# robot.net
KiCad netlist of a schematic drawn in EAGLE
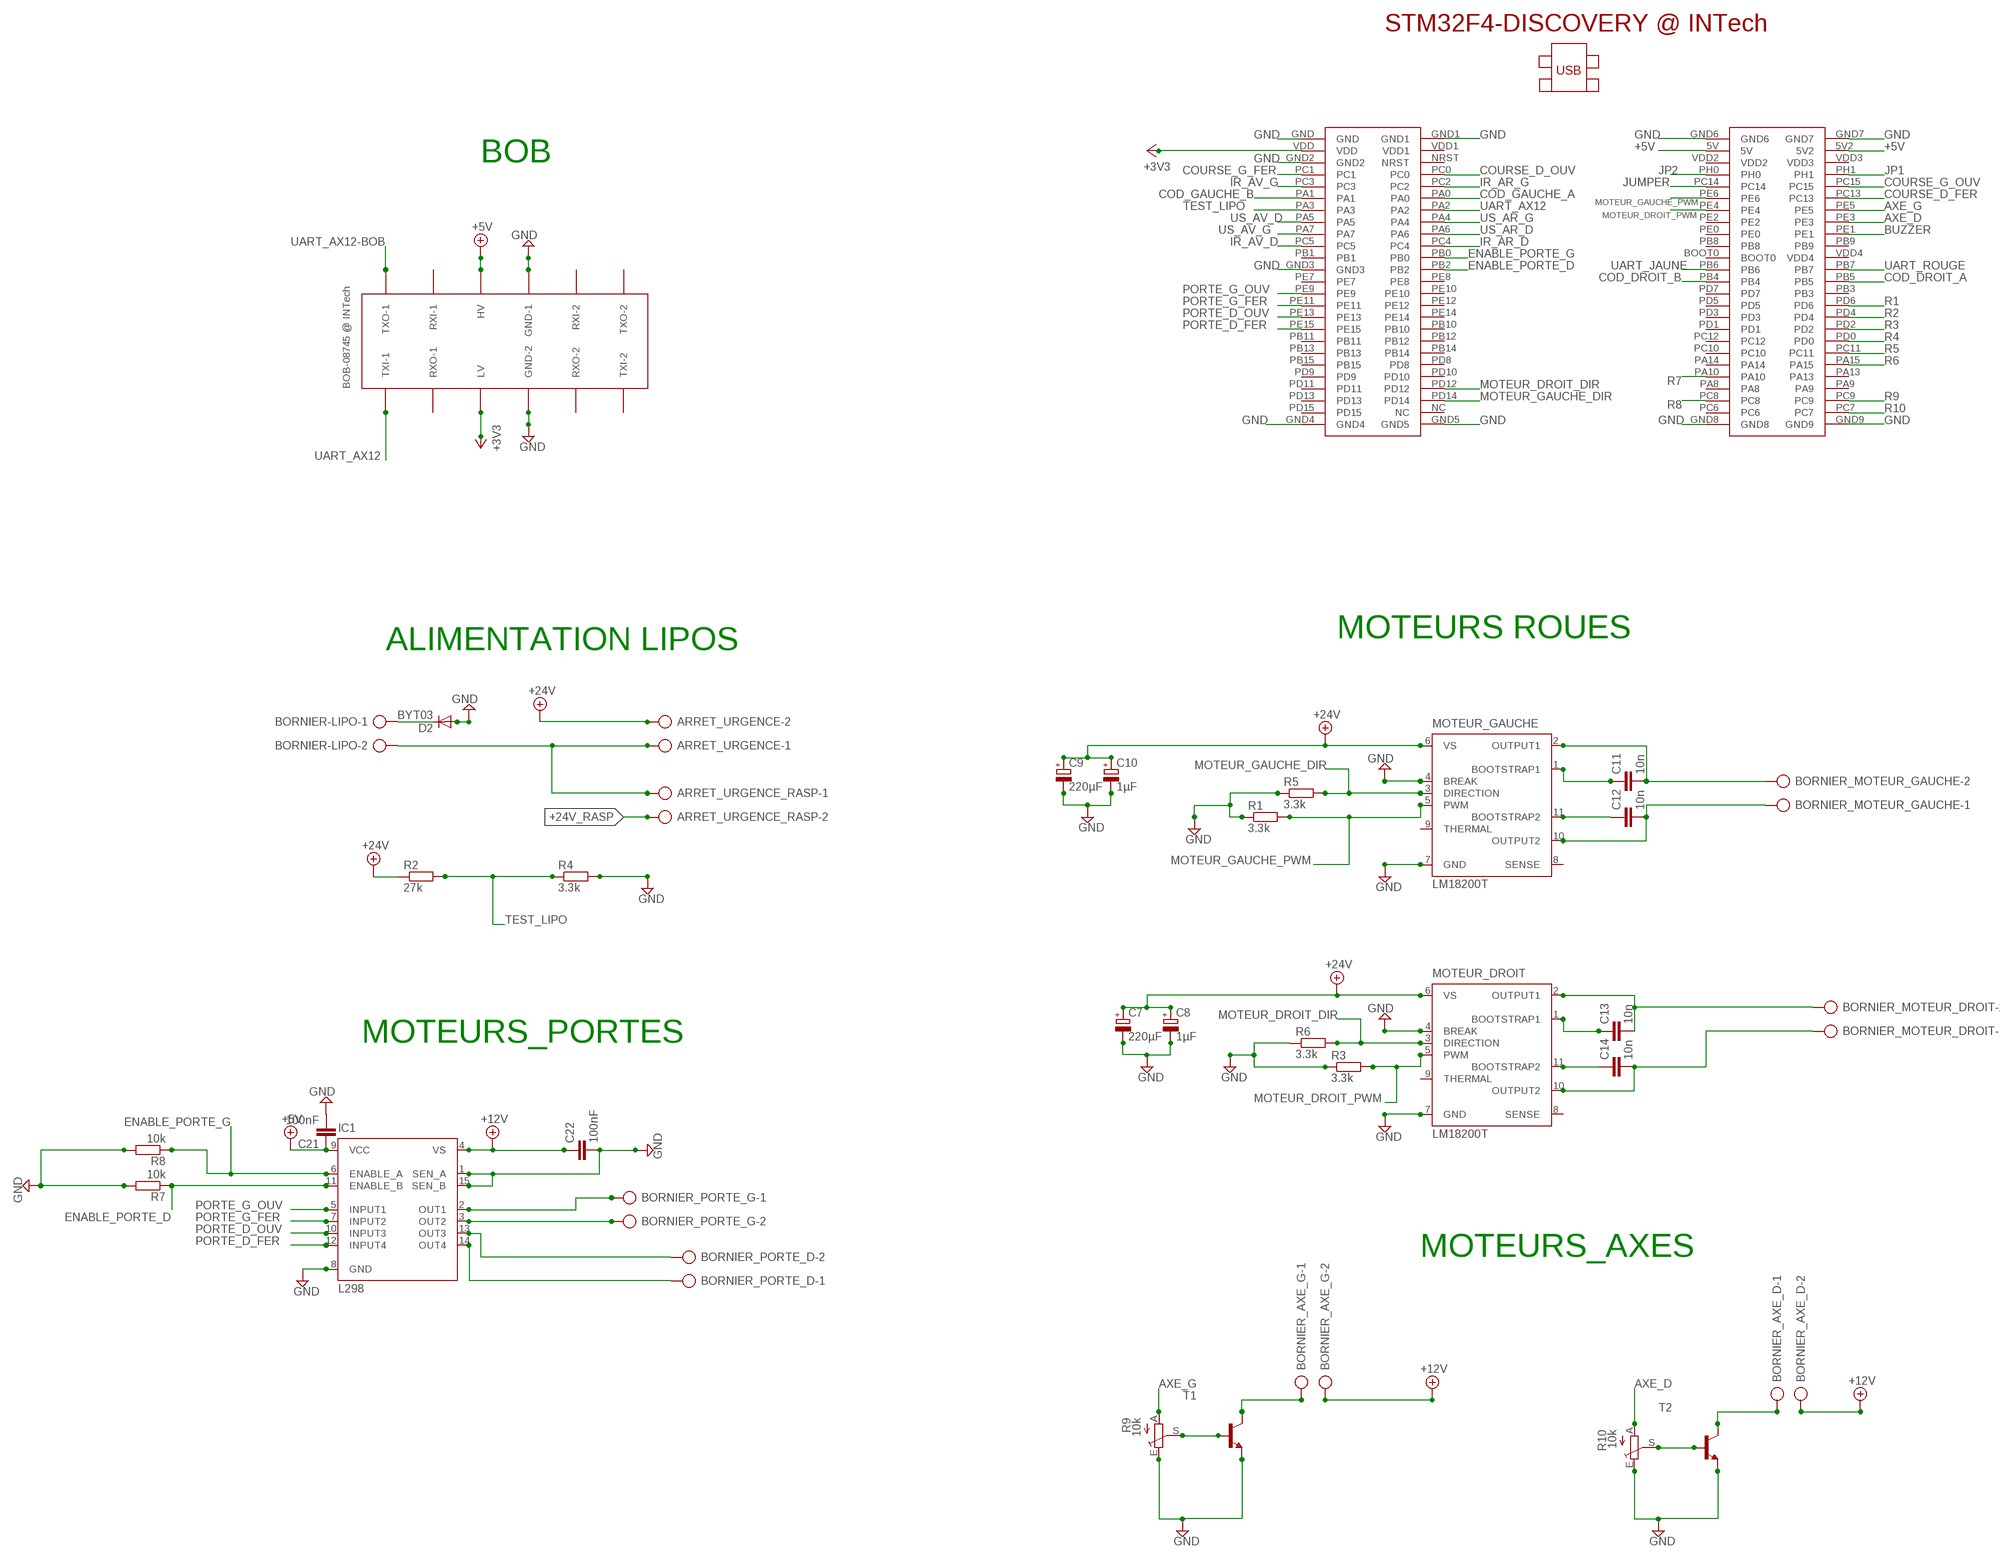
[diagram p0: schematic, sheet 1, part 1 of 2]
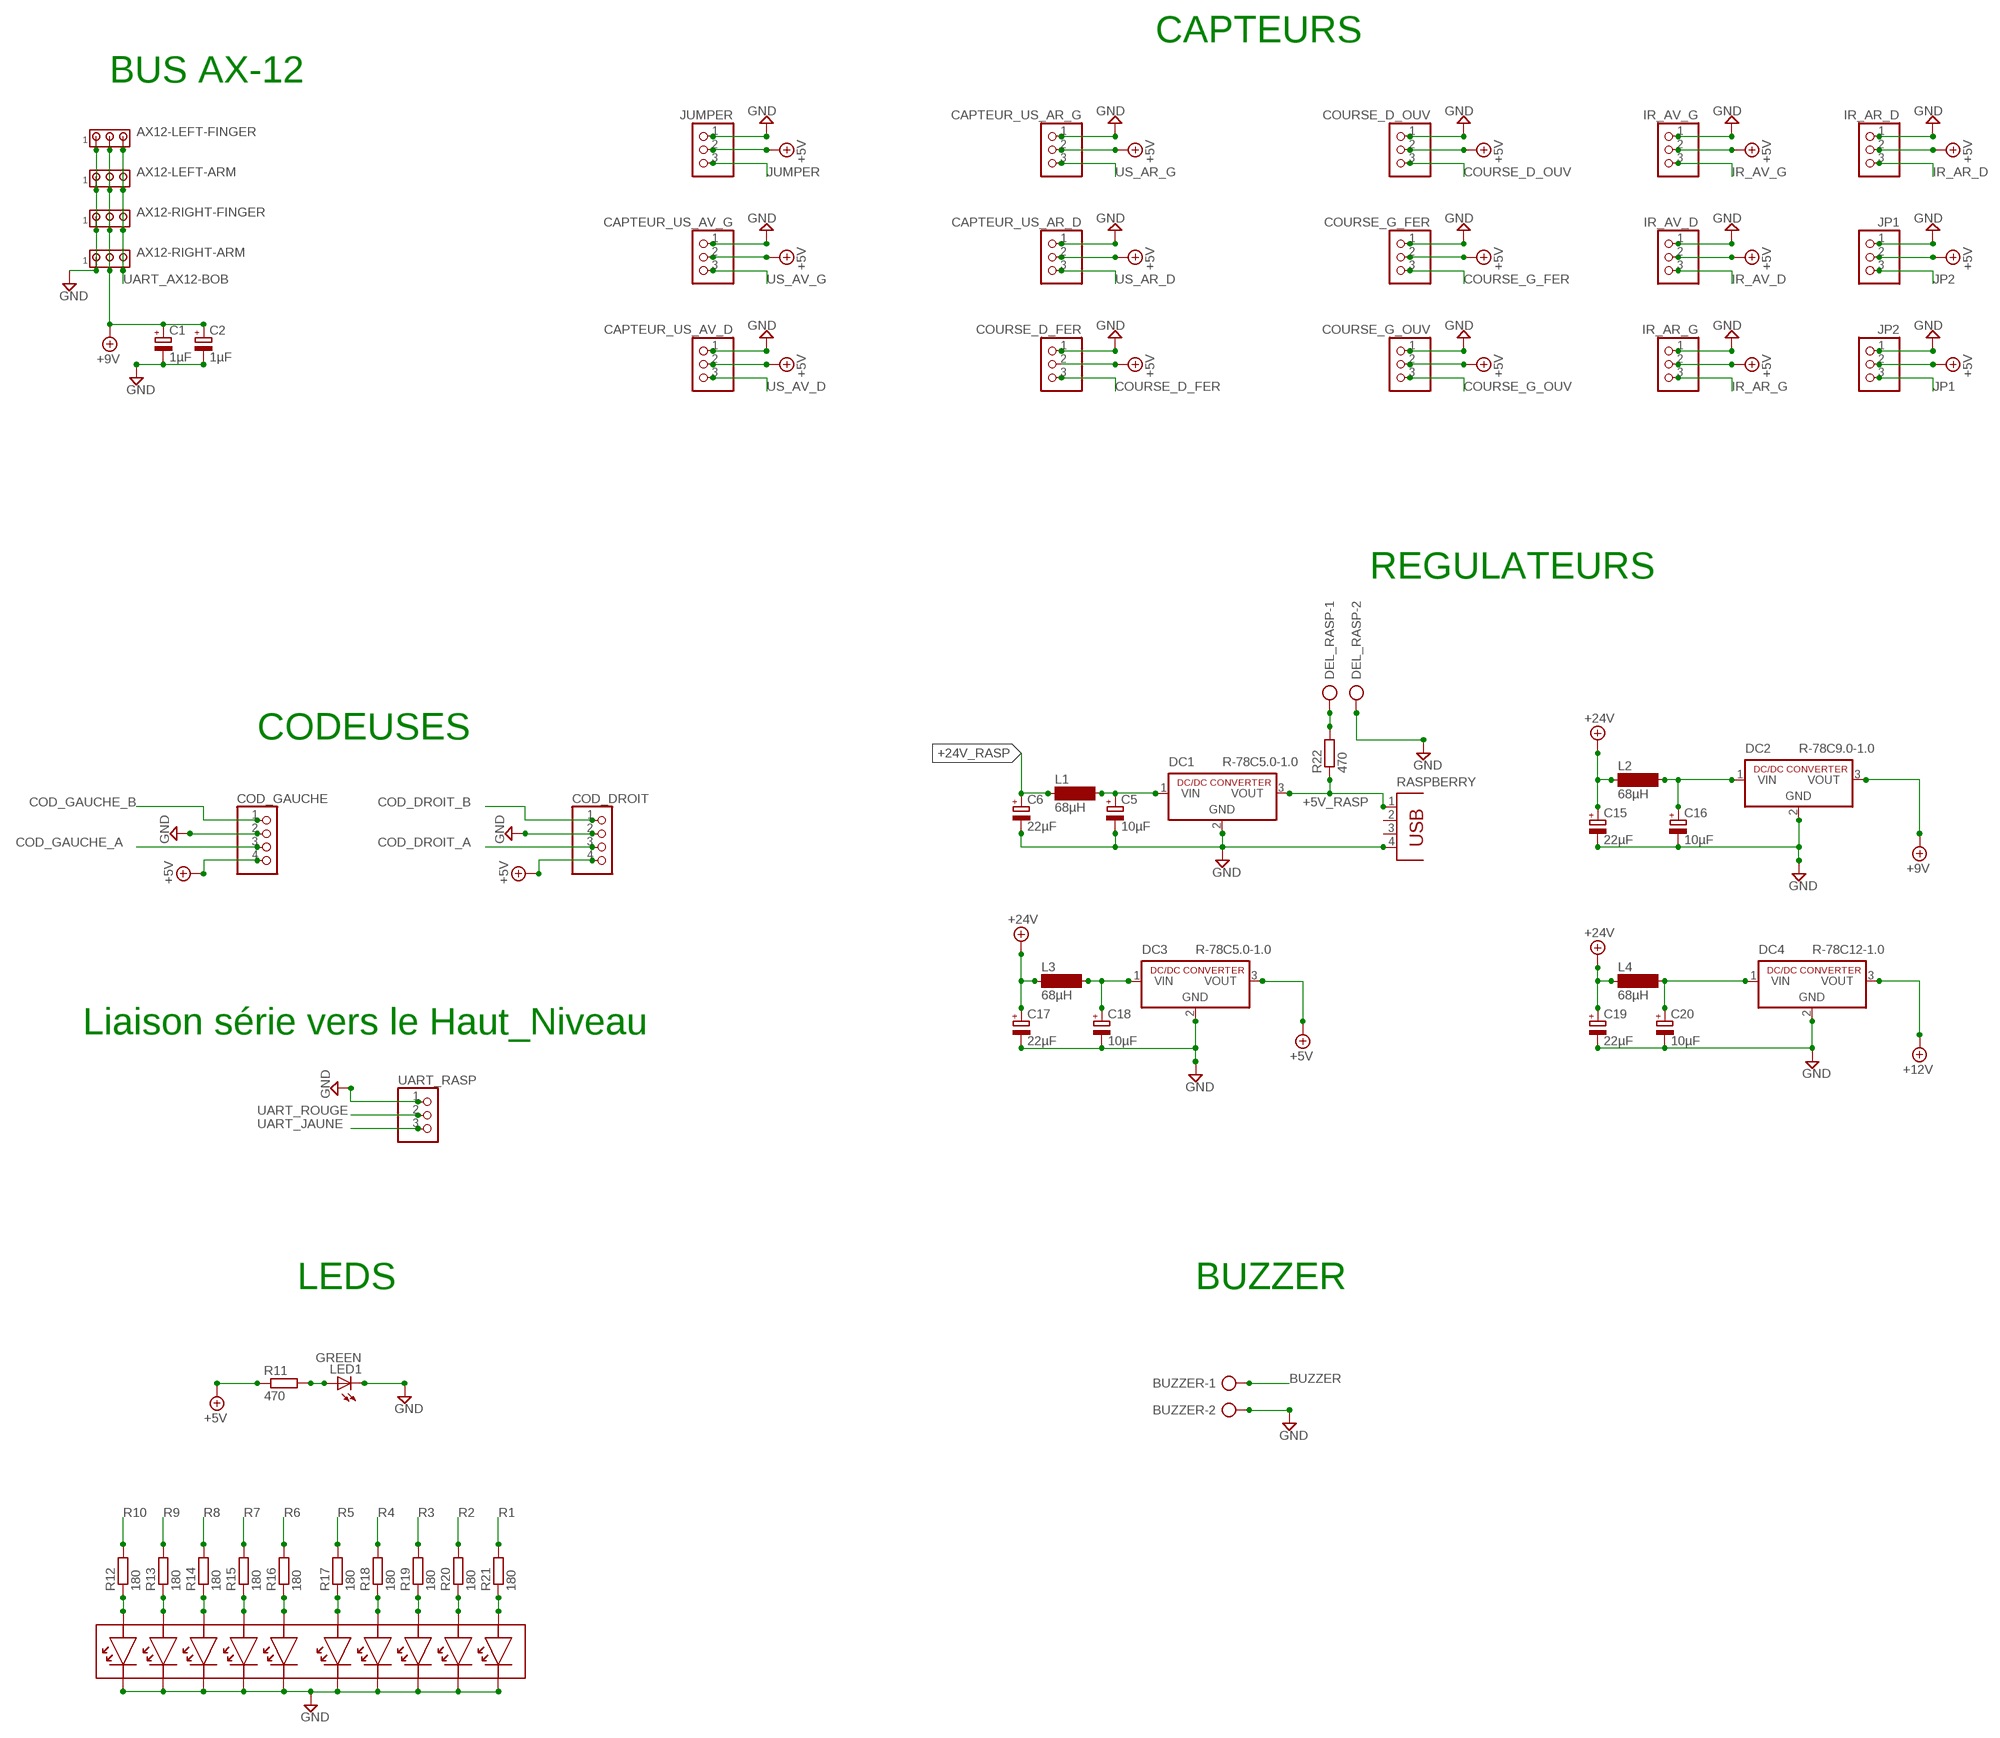
[diagram p1: schematic, sheet 1, part 2 of 2]

(export (version "E")
  (design (tool "Eeschema 10.0.6"))
  (components
    (comp (ref "ARRET_URGENCE")
      (value "AK300/2")
      (footprint "eagle-import:AK300_2")
      (libsource (lib "eagle-import") (part "AK300/2"))
    )
    (comp (ref "ARRET_URGENCE_RASP")
      (value "AK300/2")
      (footprint "eagle-import:AK300_2")
      (fields (field (name "OC_FARNELL") "unknown") (field (name "OC_NEWARK") "unknown"))
      (libsource (lib "eagle-import") (part "AK300/2"))
    )
    (comp (ref "AX12-LEFT-ARM")
      (value "MTA03-100")
      (footprint "eagle-import:10X03MTA")
      (libsource (lib "eagle-import") (part "MTA03-100"))
    )
    (comp (ref "AX12-LEFT-FINGER")
      (value "MTA03-100")
      (footprint "eagle-import:10X03MTA")
      (libsource (lib "eagle-import") (part "MTA03-100"))
    )
    (comp (ref "AX12-RIGHT-ARM")
      (value "MTA03-100")
      (footprint "eagle-import:10X03MTA")
      (libsource (lib "eagle-import") (part "MTA03-100"))
    )
    (comp (ref "AX12-RIGHT-FINGER")
      (value "MTA03-100")
      (footprint "eagle-import:10X03MTA")
      (libsource (lib "eagle-import") (part "MTA03-100"))
    )
    (comp (ref "BOB-08745")
      (value "BOB-08745")
      (footprint "eagle-import:BOB-08745")
      (libsource (lib "eagle-import") (part "BOB-08745"))
    )
    (comp (ref "BORNIER-LIPO")
      (value "AK300/2")
      (footprint "eagle-import:AK300_2")
      (libsource (lib "eagle-import") (part "AK300/2"))
    )
    (comp (ref "BORNIER_AXE_D")
      (value "AK300/2")
      (footprint "eagle-import:AK300_2")
      (fields (field (name "OC_FARNELL") "unknown") (field (name "OC_NEWARK") "unknown"))
      (libsource (lib "eagle-import") (part "AK300/2"))
    )
    (comp (ref "BORNIER_AXE_G")
      (value "AK300/2")
      (footprint "eagle-import:AK300_2")
      (fields (field (name "OC_FARNELL") "unknown") (field (name "OC_NEWARK") "unknown"))
      (libsource (lib "eagle-import") (part "AK300/2"))
    )
    (comp (ref "BORNIER_MOTEUR_DROIT")
      (value "AK300/2")
      (footprint "eagle-import:AK300_2")
      (libsource (lib "eagle-import") (part "AK300/2"))
    )
    (comp (ref "BORNIER_MOTEUR_GAUCHE")
      (value "AK300/2")
      (footprint "eagle-import:AK300_2")
      (libsource (lib "eagle-import") (part "AK300/2"))
    )
    (comp (ref "BORNIER_PORTE_D")
      (value "AK300/2")
      (footprint "eagle-import:AK300_2")
      (fields (field (name "OC_FARNELL") "unknown") (field (name "OC_NEWARK") "unknown"))
      (libsource (lib "eagle-import") (part "AK300/2"))
    )
    (comp (ref "BORNIER_PORTE_G")
      (value "AK300/2")
      (footprint "eagle-import:AK300_2")
      (fields (field (name "OC_FARNELL") "unknown") (field (name "OC_NEWARK") "unknown"))
      (libsource (lib "eagle-import") (part "AK300/2"))
    )
    (comp (ref "BUZZER")
      (value "AK300/2")
      (footprint "eagle-import:AK300_2")
      (libsource (lib "eagle-import") (part "AK300/2"))
    )
    (comp (ref "C1")
      (value "1µF")
      (footprint "eagle-import:E2,5-6E")
      (libsource (lib "eagle-import") (part "resistor_CPOL-EUE2,5-6E"))
    )
    (comp (ref "C2")
      (value "1µF")
      (footprint "eagle-import:E2,5-6E")
      (libsource (lib "eagle-import") (part "resistor_CPOL-EUE2,5-6E"))
    )
    (comp (ref "C5")
      (value "10µF")
      (footprint "eagle-import:E2,5-6E")
      (libsource (lib "eagle-import") (part "resistor_CPOL-EUE2,5-6E"))
    )
    (comp (ref "C6")
      (value "22µF")
      (footprint "eagle-import:E2,5-6E")
      (libsource (lib "eagle-import") (part "resistor_CPOL-EUE2,5-6E"))
    )
    (comp (ref "C7")
      (value "220µF")
      (footprint "eagle-import:E3,5-8")
      (libsource (lib "eagle-import") (part "CPOL-EUE3.5-8"))
    )
    (comp (ref "C8")
      (value "1µF")
      (footprint "eagle-import:E3,5-8")
      (libsource (lib "eagle-import") (part "CPOL-EUE3.5-8"))
    )
    (comp (ref "C9")
      (value "220µF")
      (footprint "eagle-import:E3,5-8")
      (libsource (lib "eagle-import") (part "CPOL-EUE3.5-8"))
    )
    (comp (ref "C10")
      (value "1µF")
      (footprint "eagle-import:E3,5-8")
      (libsource (lib "eagle-import") (part "CPOL-EUE3.5-8"))
    )
    (comp (ref "C11")
      (value "10n")
      (footprint "eagle-import:C050-025X075")
      (libsource (lib "eagle-import") (part "C-EU050-025X075"))
    )
    (comp (ref "C12")
      (value "10n")
      (footprint "eagle-import:C050-025X075")
      (libsource (lib "eagle-import") (part "C-EU050-025X075"))
    )
    (comp (ref "C13")
      (value "10n")
      (footprint "eagle-import:C050-025X075")
      (libsource (lib "eagle-import") (part "C-EU050-025X075"))
    )
    (comp (ref "C14")
      (value "10n")
      (footprint "eagle-import:C050-025X075")
      (libsource (lib "eagle-import") (part "C-EU050-025X075"))
    )
    (comp (ref "C15")
      (value "22µF")
      (footprint "eagle-import:E2,5-6E")
      (libsource (lib "eagle-import") (part "resistor_CPOL-EUE2,5-6E"))
    )
    (comp (ref "C16")
      (value "10µF")
      (footprint "eagle-import:E2,5-6E")
      (libsource (lib "eagle-import") (part "resistor_CPOL-EUE2,5-6E"))
    )
    (comp (ref "C17")
      (value "22µF")
      (footprint "eagle-import:E2,5-6E")
      (libsource (lib "eagle-import") (part "resistor_CPOL-EUE2,5-6E"))
    )
    (comp (ref "C18")
      (value "10µF")
      (footprint "eagle-import:E2,5-6E")
      (libsource (lib "eagle-import") (part "resistor_CPOL-EUE2,5-6E"))
    )
    (comp (ref "C19")
      (value "22µF")
      (footprint "eagle-import:E2,5-6E")
      (libsource (lib "eagle-import") (part "resistor_CPOL-EUE2,5-6E"))
    )
    (comp (ref "C20")
      (value "10µF")
      (footprint "eagle-import:E2,5-6E")
      (libsource (lib "eagle-import") (part "resistor_CPOL-EUE2,5-6E"))
    )
    (comp (ref "C21")
      (value "100nF")
      (footprint "eagle-import:C050-024X044")
      (libsource (lib "eagle-import") (part "resistor_C-EU050-024X044"))
    )
    (comp (ref "C22")
      (value "100nF")
      (footprint "eagle-import:C050-024X044")
      (libsource (lib "eagle-import") (part "resistor_C-EU050-024X044"))
    )
    (comp (ref "CAPTEUR_US_AR_D")
      (value "PINHD-1X3")
      (footprint "eagle-import:1X03")
      (libsource (lib "eagle-import") (part "PINHD-1X3"))
    )
    (comp (ref "CAPTEUR_US_AR_G")
      (value "PINHD-1X3")
      (footprint "eagle-import:1X03")
      (libsource (lib "eagle-import") (part "PINHD-1X3"))
    )
    (comp (ref "CAPTEUR_US_AV_D")
      (value "PINHD-1X3")
      (footprint "eagle-import:1X03")
      (libsource (lib "eagle-import") (part "PINHD-1X3"))
    )
    (comp (ref "CAPTEUR_US_AV_G")
      (value "PINHD-1X3")
      (footprint "eagle-import:1X03")
      (libsource (lib "eagle-import") (part "PINHD-1X3"))
    )
    (comp (ref "COD_DROIT")
      (value "PINHD-1X4")
      (footprint "eagle-import:1X04")
      (libsource (lib "eagle-import") (part "PINHD-1X4"))
    )
    (comp (ref "COD_GAUCHE")
      (value "PINHD-1X4")
      (footprint "eagle-import:1X04")
      (libsource (lib "eagle-import") (part "PINHD-1X4"))
    )
    (comp (ref "COURSE_D_FER")
      (value "PINHD-1X3")
      (footprint "eagle-import:1X03")
      (libsource (lib "eagle-import") (part "PINHD-1X3"))
    )
    (comp (ref "COURSE_D_OUV")
      (value "PINHD-1X3")
      (footprint "eagle-import:1X03")
      (libsource (lib "eagle-import") (part "PINHD-1X3"))
    )
    (comp (ref "COURSE_G_FER")
      (value "PINHD-1X3")
      (footprint "eagle-import:1X03")
      (libsource (lib "eagle-import") (part "PINHD-1X3"))
    )
    (comp (ref "COURSE_G_OUV")
      (value "PINHD-1X3")
      (footprint "eagle-import:1X03")
      (libsource (lib "eagle-import") (part "PINHD-1X3"))
    )
    (comp (ref "D2")
      (value "BYT03")
      (footprint "eagle-import:DO27-15")
      (libsource (lib "eagle-import") (part "BYT03"))
    )
    (comp (ref "DC1")
      (value "R-78C5.0-1.0")
      (footprint "eagle-import:SIP3")
      (libsource (lib "eagle-import") (part "R-78C-1.05.0"))
    )
    (comp (ref "DC2")
      (value "R-78C9.0-1.0")
      (footprint "eagle-import:SIP3")
      (libsource (lib "eagle-import") (part "R-78C-1.09.0"))
    )
    (comp (ref "DC3")
      (value "R-78C5.0-1.0")
      (footprint "eagle-import:SIP3")
      (libsource (lib "eagle-import") (part "R-78C-1.05.0"))
    )
    (comp (ref "DC4")
      (value "R-78C12-1.0")
      (footprint "eagle-import:SIP3")
      (libsource (lib "eagle-import") (part "R-78C-1.012"))
    )
    (comp (ref "DEL_RASP")
      (value "AK300/2")
      (footprint "eagle-import:AK300_2")
      (libsource (lib "eagle-import") (part "AK300/2"))
    )
    (comp (ref "IC1")
      (value "L298")
      (footprint "eagle-import:MULTIWATT-15")
      (fields (field (name "MPN") "L298N"))
      (libsource (lib "eagle-import") (part "L298"))
    )
    (comp (ref "IR_AR_D")
      (value "PINHD-1X3")
      (footprint "eagle-import:1X03")
      (libsource (lib "eagle-import") (part "PINHD-1X3"))
    )
    (comp (ref "IR_AR_G")
      (value "PINHD-1X3")
      (footprint "eagle-import:1X03")
      (libsource (lib "eagle-import") (part "PINHD-1X3"))
    )
    (comp (ref "IR_AV_D")
      (value "PINHD-1X3")
      (footprint "eagle-import:1X03")
      (libsource (lib "eagle-import") (part "PINHD-1X3"))
    )
    (comp (ref "IR_AV_G")
      (value "PINHD-1X3")
      (footprint "eagle-import:1X03")
      (libsource (lib "eagle-import") (part "PINHD-1X3"))
    )
    (comp (ref "JP1")
      (value "PINHD-1X3")
      (footprint "eagle-import:1X03")
      (libsource (lib "eagle-import") (part "PINHD-1X3"))
    )
    (comp (ref "JP2")
      (value "PINHD-1X3")
      (footprint "eagle-import:1X03")
      (libsource (lib "eagle-import") (part "PINHD-1X3"))
    )
    (comp (ref "JUMPER")
      (value "PINHD-1X3")
      (footprint "eagle-import:1X03")
      (libsource (lib "eagle-import") (part "PINHD-1X3"))
    )
    (comp (ref "L1")
      (value "68µH")
      (footprint "eagle-import:SD12K100")
      (libsource (lib "eagle-import") (part "SD12K100"))
    )
    (comp (ref "L2")
      (value "68µH")
      (footprint "eagle-import:SD12K100")
      (fields (field (name "OC_FARNELL") "unknown") (field (name "OC_NEWARK") "unknown"))
      (libsource (lib "eagle-import") (part "SD12K100"))
    )
    (comp (ref "L3")
      (value "68µH")
      (footprint "eagle-import:SD12K100")
      (fields (field (name "OC_FARNELL") "unknown") (field (name "OC_NEWARK") "unknown"))
      (libsource (lib "eagle-import") (part "SD12K100"))
    )
    (comp (ref "L4")
      (value "68µH")
      (footprint "eagle-import:SD12K100")
      (fields (field (name "OC_FARNELL") "unknown") (field (name "OC_NEWARK") "unknown"))
      (libsource (lib "eagle-import") (part "SD12K100"))
    )
    (comp (ref "LED1")
      (value "GREEN")
      (footprint "eagle-import:LED5MM")
      (libsource (lib "eagle-import") (part "LED5MM"))
    )
    (comp (ref "MOTEUR_DROIT")
      (value "LM18200T")
      (footprint "eagle-import:TO-220-11")
      (libsource (lib "eagle-import") (part "LM18200T"))
    )
    (comp (ref "MOTEUR_GAUCHE")
      (value "LM18200T")
      (footprint "eagle-import:TO-220-11")
      (libsource (lib "eagle-import") (part "LM18200T"))
    )
    (comp (ref "R1")
      (value "3.3k")
      (footprint "eagle-import:0207_7")
      (libsource (lib "eagle-import") (part "R-EU_0207/7"))
    )
    (comp (ref "R2")
      (value "27k")
      (footprint "eagle-import:0207_10")
      (libsource (lib "eagle-import") (part "R-EU_0207/10"))
    )
    (comp (ref "R3")
      (value "3.3k")
      (footprint "eagle-import:0207_7")
      (libsource (lib "eagle-import") (part "R-EU_0207/7"))
    )
    (comp (ref "R4")
      (value "3.3k")
      (footprint "eagle-import:0207_10")
      (libsource (lib "eagle-import") (part "R-EU_0207/10"))
    )
    (comp (ref "R5")
      (value "3.3k")
      (footprint "eagle-import:0207_10")
      (libsource (lib "eagle-import") (part "R-EU_0207/10"))
    )
    (comp (ref "R6")
      (value "3.3k")
      (footprint "eagle-import:0207_10")
      (libsource (lib "eagle-import") (part "R-EU_0207/10"))
    )
    (comp (ref "R7")
      (value "10k")
      (footprint "eagle-import:0207_10")
      (libsource (lib "eagle-import") (part "R-EU_0207/10"))
    )
    (comp (ref "R8")
      (value "10k")
      (footprint "eagle-import:0207_10")
      (libsource (lib "eagle-import") (part "R-EU_0207/10"))
    )
    (comp (ref "R9")
      (value "10k")
      (footprint "eagle-import:CA9H")
      (libsource (lib "eagle-import") (part "TRIM_EU-CA9H"))
    )
    (comp (ref "R10")
      (value "10k")
      (footprint "eagle-import:CA9H")
      (libsource (lib "eagle-import") (part "TRIM_EU-CA9H"))
    )
    (comp (ref "R11")
      (value "470")
      (footprint "eagle-import:0207_2V")
      (libsource (lib "eagle-import") (part "R-EU_0207/2V"))
    )
    (comp (ref "R12")
      (value "180")
      (footprint "eagle-import:0207_2V")
      (libsource (lib "eagle-import") (part "R-EU_0207/2V"))
    )
    (comp (ref "R13")
      (value "180")
      (footprint "eagle-import:0207_2V")
      (libsource (lib "eagle-import") (part "R-EU_0207/2V"))
    )
    (comp (ref "R14")
      (value "180")
      (footprint "eagle-import:0207_2V")
      (libsource (lib "eagle-import") (part "R-EU_0207/2V"))
    )
    (comp (ref "R15")
      (value "180")
      (footprint "eagle-import:0207_2V")
      (libsource (lib "eagle-import") (part "R-EU_0207/2V"))
    )
    (comp (ref "R16")
      (value "180")
      (footprint "eagle-import:0207_2V")
      (libsource (lib "eagle-import") (part "R-EU_0207/2V"))
    )
    (comp (ref "R17")
      (value "180")
      (footprint "eagle-import:0207_2V")
      (libsource (lib "eagle-import") (part "R-EU_0207/2V"))
    )
    (comp (ref "R18")
      (value "180")
      (footprint "eagle-import:0207_2V")
      (libsource (lib "eagle-import") (part "R-EU_0207/2V"))
    )
    (comp (ref "R19")
      (value "180")
      (footprint "eagle-import:0207_2V")
      (libsource (lib "eagle-import") (part "R-EU_0207/2V"))
    )
    (comp (ref "R20")
      (value "180")
      (footprint "eagle-import:0207_2V")
      (libsource (lib "eagle-import") (part "R-EU_0207/2V"))
    )
    (comp (ref "R21")
      (value "180")
      (footprint "eagle-import:0207_2V")
      (libsource (lib "eagle-import") (part "R-EU_0207/2V"))
    )
    (comp (ref "R22")
      (value "470")
      (footprint "eagle-import:0204_7")
      (libsource (lib "eagle-import") (part "R-EU_0204/7"))
    )
    (comp (ref "RASPBERRY")
      (value "PN87520")
      (footprint "eagle-import:PN87520")
      (libsource (lib "eagle-import") (part "PN87520"))
    )
    (comp (ref "T1")
      (value "2N5400-NPN-TO92-CBE")
      (footprint "eagle-import:TO92-CBE")
      (libsource (lib "eagle-import") (part "-NPN-TO92-CBE2N5400"))
    )
    (comp (ref "T2")
      (value "2N5400-NPN-TO92-CBE")
      (footprint "eagle-import:TO92-CBE")
      (libsource (lib "eagle-import") (part "-NPN-TO92-CBE2N5400"))
    )
    (comp (ref "U$1")
      (value "STM32F4-DISCOVERY")
      (footprint "eagle-import:STM32F4-DISCOVERY")
      (libsource (lib "eagle-import") (part "STM32F4-DISCOVERY"))
    )
    (comp (ref "U$2")
      (value "DELS10RACK")
      (footprint "eagle-import:DELS10RACK")
      (libsource (lib "eagle-import") (part "DELS10RACK"))
    )
    (comp (ref "UART_RASP")
      (value "PINHD-1X3")
      (footprint "eagle-import:1X03")
      (libsource (lib "eagle-import") (part "PINHD-1X3"))
    )
  )
  (nets
    (net (code "1") (name "+3V3") (class "Default")
      (node (ref "BOB-08745") (pin "LV") (pinfunction "LV_LV") (pintype "bidirectional"))
      (node (ref "U$1") (pin "VDD") (pinfunction "VDD_VDD") (pintype "bidirectional"))
    )
    (net (code "2") (name "+5V") (class "Default")
      (node (ref "BOB-08745") (pin "HV") (pinfunction "HV_HV") (pintype "bidirectional"))
      (node (ref "C21") (pin "1") (pinfunction "1_1") (pintype "passive"))
      (node (ref "CAPTEUR_US_AR_D") (pin "2") (pinfunction "2_2") (pintype "passive"))
      (node (ref "CAPTEUR_US_AR_G") (pin "2") (pinfunction "2_2") (pintype "passive"))
      (node (ref "CAPTEUR_US_AV_D") (pin "2") (pinfunction "2_2") (pintype "passive"))
      (node (ref "CAPTEUR_US_AV_G") (pin "2") (pinfunction "2_2") (pintype "passive"))
      (node (ref "COD_DROIT") (pin "4") (pinfunction "4_4") (pintype "passive"))
      (node (ref "COD_GAUCHE") (pin "4") (pinfunction "4_4") (pintype "passive"))
      (node (ref "COURSE_D_FER") (pin "2") (pinfunction "2_2") (pintype "passive"))
      (node (ref "COURSE_D_OUV") (pin "2") (pinfunction "2_2") (pintype "passive"))
      (node (ref "COURSE_G_FER") (pin "2") (pinfunction "2_2") (pintype "passive"))
      (node (ref "COURSE_G_OUV") (pin "2") (pinfunction "2_2") (pintype "passive"))
      (node (ref "DC3") (pin "3") (pinfunction "VOUT_3") (pintype "passive"))
      (node (ref "IC1") (pin "9") (pinfunction "VCC_9") (pintype "power_in"))
      (node (ref "IR_AR_D") (pin "2") (pinfunction "2_2") (pintype "passive"))
      (node (ref "IR_AR_G") (pin "2") (pinfunction "2_2") (pintype "passive"))
      (node (ref "IR_AV_D") (pin "2") (pinfunction "2_2") (pintype "passive"))
      (node (ref "IR_AV_G") (pin "2") (pinfunction "2_2") (pintype "passive"))
      (node (ref "JP1") (pin "2") (pinfunction "2_2") (pintype "passive"))
      (node (ref "JP2") (pin "2") (pinfunction "2_2") (pintype "passive"))
      (node (ref "JUMPER") (pin "2") (pinfunction "2_2") (pintype "passive"))
      (node (ref "R11") (pin "1") (pinfunction "1_1") (pintype "passive"))
      (node (ref "U$1") (pin "5V") (pinfunction "5V_5V") (pintype "bidirectional"))
      (node (ref "U$1") (pin "5V2") (pinfunction "5V2_5V2") (pintype "bidirectional"))
    )
    (net (code "3") (name "+9V") (class "Default")
      (node (ref "AX12-LEFT-ARM") (pin "2") (pinfunction "2_2") (pintype "passive"))
      (node (ref "AX12-LEFT-FINGER") (pin "2") (pinfunction "2_2") (pintype "passive"))
      (node (ref "AX12-RIGHT-ARM") (pin "2") (pinfunction "2_2") (pintype "passive"))
      (node (ref "AX12-RIGHT-FINGER") (pin "2") (pinfunction "2_2") (pintype "passive"))
      (node (ref "C1") (pin "+") (pinfunction "+_+") (pintype "passive"))
      (node (ref "C2") (pin "+") (pinfunction "+_+") (pintype "passive"))
      (node (ref "DC2") (pin "3") (pinfunction "VOUT_3") (pintype "passive"))
    )
    (net (code "4") (name "+12V") (class "Default")
      (node (ref "BORNIER_AXE_D") (pin "2") (pinfunction "KL_2") (pintype "passive"))
      (node (ref "BORNIER_AXE_G") (pin "2") (pinfunction "KL_2") (pintype "passive"))
      (node (ref "C22") (pin "1") (pinfunction "1_1") (pintype "passive"))
      (node (ref "DC4") (pin "3") (pinfunction "VOUT_3") (pintype "passive"))
      (node (ref "IC1") (pin "4") (pinfunction "VS_4") (pintype "power_in"))
    )
    (net (code "5") (name "+24V") (class "Default")
      (node (ref "ARRET_URGENCE") (pin "2") (pinfunction "KL_2") (pintype "passive"))
      (node (ref "C10") (pin "+") (pinfunction "+_+") (pintype "passive"))
      (node (ref "C15") (pin "+") (pinfunction "+_+") (pintype "passive"))
      (node (ref "C17") (pin "+") (pinfunction "+_+") (pintype "passive"))
      (node (ref "C19") (pin "+") (pinfunction "+_+") (pintype "passive"))
      (node (ref "C7") (pin "+") (pinfunction "+_+") (pintype "passive"))
      (node (ref "C8") (pin "+") (pinfunction "+_+") (pintype "passive"))
      (node (ref "C9") (pin "+") (pinfunction "+_+") (pintype "passive"))
      (node (ref "L2") (pin "1") (pinfunction "1_1") (pintype "passive"))
      (node (ref "L3") (pin "1") (pinfunction "1_1") (pintype "passive"))
      (node (ref "L4") (pin "1") (pinfunction "1_1") (pintype "passive"))
      (node (ref "MOTEUR_DROIT") (pin "6") (pinfunction "VS_6") (pintype "power_in"))
      (node (ref "MOTEUR_GAUCHE") (pin "6") (pinfunction "VS_6") (pintype "power_in"))
      (node (ref "R2") (pin "1") (pinfunction "1_1") (pintype "passive"))
    )
    (net (code "6") (name "+24V_RASP") (class "Default")
      (node (ref "ARRET_URGENCE_RASP") (pin "2") (pinfunction "KL_2") (pintype "passive"))
      (node (ref "C6") (pin "+") (pinfunction "+_+") (pintype "passive"))
      (node (ref "L1") (pin "1") (pinfunction "1_1") (pintype "passive"))
    )
    (net (code "7") (name "/+5V_RASP") (class "Default")
      (node (ref "DC1") (pin "3") (pinfunction "VOUT_3") (pintype "passive"))
      (node (ref "R22") (pin "1") (pinfunction "1_1") (pintype "passive"))
      (node (ref "RASPBERRY") (pin "1") (pinfunction "1_1") (pintype "passive"))
    )
    (net (code "8") (name "/AXE_D") (class "Default")
      (node (ref "R10") (pin "A") (pinfunction "A_A") (pintype "passive"))
      (node (ref "U$1") (pin "PE3") (pinfunction "PE3_PE3") (pintype "bidirectional"))
    )
    (net (code "9") (name "/AXE_G") (class "Default")
      (node (ref "R9") (pin "A") (pinfunction "A_A") (pintype "passive"))
      (node (ref "U$1") (pin "PE5") (pinfunction "PE5_PE5") (pintype "bidirectional"))
    )
    (net (code "10") (name "/BUZZER") (class "Default")
      (node (ref "BUZZER") (pin "1") (pinfunction "KL_1") (pintype "passive"))
      (node (ref "U$1") (pin "PE1") (pinfunction "PE1_PE1") (pintype "bidirectional"))
    )
    (net (code "11") (name "/COD_DROIT_A") (class "Default")
      (node (ref "COD_DROIT") (pin "3") (pinfunction "3_3") (pintype "passive"))
      (node (ref "U$1") (pin "PB5") (pinfunction "PB5_PB5") (pintype "bidirectional"))
    )
    (net (code "12") (name "/COD_DROIT_B") (class "Default")
      (node (ref "COD_DROIT") (pin "1") (pinfunction "1_1") (pintype "passive"))
      (node (ref "U$1") (pin "PB4") (pinfunction "PB4_PB4") (pintype "bidirectional"))
    )
    (net (code "13") (name "/COD_GAUCHE_A") (class "Default")
      (node (ref "COD_GAUCHE") (pin "3") (pinfunction "3_3") (pintype "passive"))
      (node (ref "U$1") (pin "PA0") (pinfunction "PA0_PA0") (pintype "bidirectional"))
    )
    (net (code "14") (name "/COD_GAUCHE_B") (class "Default")
      (node (ref "COD_GAUCHE") (pin "1") (pinfunction "1_1") (pintype "passive"))
      (node (ref "U$1") (pin "PA1") (pinfunction "PA1_PA1") (pintype "bidirectional"))
    )
    (net (code "15") (name "/COURSE_D_FER") (class "Default")
      (node (ref "COURSE_D_FER") (pin "3") (pinfunction "3_3") (pintype "passive"))
      (node (ref "U$1") (pin "PC13") (pinfunction "PC13_PC13") (pintype "bidirectional"))
    )
    (net (code "16") (name "/COURSE_D_OUV") (class "Default")
      (node (ref "COURSE_D_OUV") (pin "3") (pinfunction "3_3") (pintype "passive"))
      (node (ref "U$1") (pin "PC0") (pinfunction "PC0_PC0") (pintype "bidirectional"))
    )
    (net (code "17") (name "/COURSE_G_FER") (class "Default")
      (node (ref "COURSE_G_FER") (pin "3") (pinfunction "3_3") (pintype "passive"))
      (node (ref "U$1") (pin "PC1") (pinfunction "PC1_PC1") (pintype "bidirectional"))
    )
    (net (code "18") (name "/COURSE_G_OUV") (class "Default")
      (node (ref "COURSE_G_OUV") (pin "3") (pinfunction "3_3") (pintype "passive"))
      (node (ref "U$1") (pin "PC15") (pinfunction "PC15_PC15") (pintype "bidirectional"))
    )
    (net (code "19") (name "/ENABLE_PORTE_D") (class "Default")
      (node (ref "IC1") (pin "11") (pinfunction "ENABLE_B_11") (pintype "input"))
      (node (ref "R7") (pin "1") (pinfunction "1_1") (pintype "passive"))
      (node (ref "U$1") (pin "PB2") (pinfunction "PB2_PB2") (pintype "bidirectional"))
    )
    (net (code "20") (name "/ENABLE_PORTE_G") (class "Default")
      (node (ref "IC1") (pin "6") (pinfunction "ENABLE_A_6") (pintype "input"))
      (node (ref "R8") (pin "1") (pinfunction "1_1") (pintype "passive"))
      (node (ref "U$1") (pin "PB0") (pinfunction "PB0_PB0") (pintype "bidirectional"))
    )
    (net (code "21") (name "/IR_AR_D") (class "Default")
      (node (ref "IR_AR_D") (pin "3") (pinfunction "3_3") (pintype "passive"))
      (node (ref "U$1") (pin "PC4") (pinfunction "PC4_PC4") (pintype "bidirectional"))
    )
    (net (code "22") (name "/IR_AR_G") (class "Default")
      (node (ref "IR_AR_G") (pin "3") (pinfunction "3_3") (pintype "passive"))
      (node (ref "U$1") (pin "PC2") (pinfunction "PC2_PC2") (pintype "bidirectional"))
    )
    (net (code "23") (name "/IR_AV_D") (class "Default")
      (node (ref "IR_AV_D") (pin "3") (pinfunction "3_3") (pintype "passive"))
      (node (ref "U$1") (pin "PC5") (pinfunction "PC5_PC5") (pintype "bidirectional"))
    )
    (net (code "24") (name "/IR_AV_G") (class "Default")
      (node (ref "IR_AV_G") (pin "3") (pinfunction "3_3") (pintype "passive"))
      (node (ref "U$1") (pin "PC3") (pinfunction "PC3_PC3") (pintype "bidirectional"))
    )
    (net (code "25") (name "/JP1") (class "Default")
      (node (ref "JP2") (pin "3") (pinfunction "3_3") (pintype "passive"))
      (node (ref "U$1") (pin "PH1") (pinfunction "PH1_PH1") (pintype "bidirectional"))
    )
    (net (code "26") (name "/JP2") (class "Default")
      (node (ref "JP1") (pin "3") (pinfunction "3_3") (pintype "passive"))
      (node (ref "U$1") (pin "PH0") (pinfunction "PH0_PH0") (pintype "bidirectional"))
    )
    (net (code "27") (name "/JUMPER") (class "Default")
      (node (ref "JUMPER") (pin "3") (pinfunction "3_3") (pintype "passive"))
      (node (ref "U$1") (pin "PC14") (pinfunction "PC14_PC14") (pintype "bidirectional"))
    )
    (net (code "28") (name "/MOTEUR_DROIT_DIR") (class "Default")
      (node (ref "MOTEUR_DROIT") (pin "3") (pinfunction "DIRECTION_3") (pintype "input"))
      (node (ref "R6") (pin "2") (pinfunction "2_2") (pintype "passive"))
      (node (ref "U$1") (pin "PD12") (pinfunction "PD12_PD12") (pintype "bidirectional"))
    )
    (net (code "29") (name "/MOTEUR_DROIT_PWM") (class "Default")
      (node (ref "MOTEUR_DROIT") (pin "5") (pinfunction "PWM_5") (pintype "input"))
      (node (ref "R3") (pin "2") (pinfunction "2_2") (pintype "passive"))
      (node (ref "U$1") (pin "PE4") (pinfunction "PE4_PE4") (pintype "bidirectional"))
    )
    (net (code "30") (name "/MOTEUR_GAUCHE_DIR") (class "Default")
      (node (ref "MOTEUR_GAUCHE") (pin "3") (pinfunction "DIRECTION_3") (pintype "input"))
      (node (ref "R5") (pin "2") (pinfunction "2_2") (pintype "passive"))
      (node (ref "U$1") (pin "PD14") (pinfunction "PD14_PD14") (pintype "bidirectional"))
    )
    (net (code "31") (name "/MOTEUR_GAUCHE_PWM") (class "Default")
      (node (ref "MOTEUR_GAUCHE") (pin "5") (pinfunction "PWM_5") (pintype "input"))
      (node (ref "R1") (pin "2") (pinfunction "2_2") (pintype "passive"))
      (node (ref "U$1") (pin "PE6") (pinfunction "PE6_PE6") (pintype "bidirectional"))
    )
    (net (code "32") (name "/PORTE_D_FER") (class "Default")
      (node (ref "IC1") (pin "12") (pinfunction "INPUT4_12") (pintype "input"))
      (node (ref "U$1") (pin "PE15") (pinfunction "PE15_PE15") (pintype "bidirectional"))
    )
    (net (code "33") (name "/PORTE_D_OUV") (class "Default")
      (node (ref "IC1") (pin "10") (pinfunction "INPUT3_10") (pintype "input"))
      (node (ref "U$1") (pin "PE13") (pinfunction "PE13_PE13") (pintype "bidirectional"))
    )
    (net (code "34") (name "/PORTE_G_FER") (class "Default")
      (node (ref "IC1") (pin "7") (pinfunction "INPUT2_7") (pintype "input"))
      (node (ref "U$1") (pin "PE11") (pinfunction "PE11_PE11") (pintype "bidirectional"))
    )
    (net (code "35") (name "/PORTE_G_OUV") (class "Default")
      (node (ref "IC1") (pin "5") (pinfunction "INPUT1_5") (pintype "input"))
      (node (ref "U$1") (pin "PE9") (pinfunction "PE9_PE9") (pintype "bidirectional"))
    )
    (net (code "36") (name "/R1") (class "Default")
      (node (ref "R21") (pin "2") (pinfunction "2_2") (pintype "passive"))
      (node (ref "U$1") (pin "PD6") (pinfunction "PD6_PD6") (pintype "bidirectional"))
    )
    (net (code "37") (name "/R2") (class "Default")
      (node (ref "R20") (pin "2") (pinfunction "2_2") (pintype "passive"))
      (node (ref "U$1") (pin "PD4") (pinfunction "PD4_PD4") (pintype "bidirectional"))
    )
    (net (code "38") (name "/R3") (class "Default")
      (node (ref "R19") (pin "2") (pinfunction "2_2") (pintype "passive"))
      (node (ref "U$1") (pin "PD2") (pinfunction "PD2_PD2") (pintype "bidirectional"))
    )
    (net (code "39") (name "/R4") (class "Default")
      (node (ref "R18") (pin "2") (pinfunction "2_2") (pintype "passive"))
      (node (ref "U$1") (pin "PD0") (pinfunction "PD0_PD0") (pintype "bidirectional"))
    )
    (net (code "40") (name "/R5") (class "Default")
      (node (ref "R17") (pin "2") (pinfunction "2_2") (pintype "passive"))
      (node (ref "U$1") (pin "PC11") (pinfunction "PC11_PC11") (pintype "bidirectional"))
    )
    (net (code "41") (name "/R6") (class "Default")
      (node (ref "R16") (pin "2") (pinfunction "2_2") (pintype "passive"))
      (node (ref "U$1") (pin "PA15") (pinfunction "PA15_PA15") (pintype "bidirectional"))
    )
    (net (code "42") (name "/R7") (class "Default")
      (node (ref "R15") (pin "2") (pinfunction "2_2") (pintype "passive"))
      (node (ref "U$1") (pin "PA10") (pinfunction "PA10_PA10") (pintype "bidirectional"))
    )
    (net (code "43") (name "/R8") (class "Default")
      (node (ref "R14") (pin "2") (pinfunction "2_2") (pintype "passive"))
      (node (ref "U$1") (pin "PC8") (pinfunction "PC8_PC8") (pintype "bidirectional"))
    )
    (net (code "44") (name "/R9") (class "Default")
      (node (ref "R13") (pin "2") (pinfunction "2_2") (pintype "passive"))
      (node (ref "U$1") (pin "PC9") (pinfunction "PC9_PC9") (pintype "bidirectional"))
    )
    (net (code "45") (name "/R10") (class "Default")
      (node (ref "R12") (pin "2") (pinfunction "2_2") (pintype "passive"))
      (node (ref "U$1") (pin "PC7") (pinfunction "PC7_PC7") (pintype "bidirectional"))
    )
    (net (code "46") (name "/TEST_LIPO") (class "Default")
      (node (ref "R2") (pin "2") (pinfunction "2_2") (pintype "passive"))
      (node (ref "R4") (pin "1") (pinfunction "1_1") (pintype "passive"))
      (node (ref "U$1") (pin "PA3") (pinfunction "PA3_PA3") (pintype "bidirectional"))
    )
    (net (code "47") (name "/UART_AX12") (class "Default")
      (node (ref "BOB-08745") (pin "TXI-1") (pinfunction "TXI-1_TXI-1") (pintype "bidirectional"))
      (node (ref "U$1") (pin "PA2") (pinfunction "PA2_PA2") (pintype "bidirectional"))
    )
    (net (code "48") (name "/UART_AX12-BOB") (class "Default")
      (node (ref "AX12-LEFT-ARM") (pin "3") (pinfunction "3_3") (pintype "passive"))
      (node (ref "AX12-LEFT-FINGER") (pin "3") (pinfunction "3_3") (pintype "passive"))
      (node (ref "AX12-RIGHT-ARM") (pin "3") (pinfunction "3_3") (pintype "passive"))
      (node (ref "AX12-RIGHT-FINGER") (pin "3") (pinfunction "3_3") (pintype "passive"))
      (node (ref "BOB-08745") (pin "TXO-1") (pinfunction "TXO-1_TXO-1") (pintype "bidirectional"))
    )
    (net (code "49") (name "/UART_JAUNE") (class "Default")
      (node (ref "U$1") (pin "PB6") (pinfunction "PB6_PB6") (pintype "bidirectional"))
      (node (ref "UART_RASP") (pin "3") (pinfunction "3_3") (pintype "passive"))
    )
    (net (code "50") (name "/UART_ROUGE") (class "Default")
      (node (ref "U$1") (pin "PB7") (pinfunction "PB7_PB7") (pintype "bidirectional"))
      (node (ref "UART_RASP") (pin "2") (pinfunction "2_2") (pintype "passive"))
    )
    (net (code "51") (name "/US_AR_D") (class "Default")
      (node (ref "CAPTEUR_US_AR_D") (pin "3") (pinfunction "3_3") (pintype "passive"))
      (node (ref "U$1") (pin "PA6") (pinfunction "PA6_PA6") (pintype "bidirectional"))
    )
    (net (code "52") (name "/US_AR_G") (class "Default")
      (node (ref "CAPTEUR_US_AR_G") (pin "3") (pinfunction "3_3") (pintype "passive"))
      (node (ref "U$1") (pin "PA4") (pinfunction "PA4_PA4") (pintype "bidirectional"))
    )
    (net (code "53") (name "/US_AV_D") (class "Default")
      (node (ref "CAPTEUR_US_AV_D") (pin "3") (pinfunction "3_3") (pintype "passive"))
      (node (ref "U$1") (pin "PA5") (pinfunction "PA5_PA5") (pintype "bidirectional"))
    )
    (net (code "54") (name "/US_AV_G") (class "Default")
      (node (ref "CAPTEUR_US_AV_G") (pin "3") (pinfunction "3_3") (pintype "passive"))
      (node (ref "U$1") (pin "PA7") (pinfunction "PA7_PA7") (pintype "bidirectional"))
    )
    (net (code "55") (name "GND") (class "Default")
      (node (ref "AX12-LEFT-ARM") (pin "1") (pinfunction "1_1") (pintype "passive"))
      (node (ref "AX12-LEFT-FINGER") (pin "1") (pinfunction "1_1") (pintype "passive"))
      (node (ref "AX12-RIGHT-ARM") (pin "1") (pinfunction "1_1") (pintype "passive"))
      (node (ref "AX12-RIGHT-FINGER") (pin "1") (pinfunction "1_1") (pintype "passive"))
      (node (ref "BOB-08745") (pin "GND-1") (pinfunction "GND-1_GND-1") (pintype "bidirectional"))
      (node (ref "BOB-08745") (pin "GND-2") (pinfunction "GND-2_GND-2") (pintype "bidirectional"))
      (node (ref "BUZZER") (pin "2") (pinfunction "KL_2") (pintype "passive"))
      (node (ref "C1") (pin "-") (pinfunction "-_-") (pintype "passive"))
      (node (ref "C10") (pin "-") (pinfunction "-_-") (pintype "passive"))
      (node (ref "C15") (pin "-") (pinfunction "-_-") (pintype "passive"))
      (node (ref "C16") (pin "-") (pinfunction "-_-") (pintype "passive"))
      (node (ref "C17") (pin "-") (pinfunction "-_-") (pintype "passive"))
      (node (ref "C18") (pin "-") (pinfunction "-_-") (pintype "passive"))
      (node (ref "C19") (pin "-") (pinfunction "-_-") (pintype "passive"))
      (node (ref "C2") (pin "-") (pinfunction "-_-") (pintype "passive"))
      (node (ref "C20") (pin "-") (pinfunction "-_-") (pintype "passive"))
      (node (ref "C21") (pin "2") (pinfunction "2_2") (pintype "passive"))
      (node (ref "C22") (pin "2") (pinfunction "2_2") (pintype "passive"))
      (node (ref "C5") (pin "-") (pinfunction "-_-") (pintype "passive"))
      (node (ref "C6") (pin "-") (pinfunction "-_-") (pintype "passive"))
      (node (ref "C7") (pin "-") (pinfunction "-_-") (pintype "passive"))
      (node (ref "C8") (pin "-") (pinfunction "-_-") (pintype "passive"))
      (node (ref "C9") (pin "-") (pinfunction "-_-") (pintype "passive"))
      (node (ref "CAPTEUR_US_AR_D") (pin "1") (pinfunction "1_1") (pintype "passive"))
      (node (ref "CAPTEUR_US_AR_G") (pin "1") (pinfunction "1_1") (pintype "passive"))
      (node (ref "CAPTEUR_US_AV_D") (pin "1") (pinfunction "1_1") (pintype "passive"))
      (node (ref "CAPTEUR_US_AV_G") (pin "1") (pinfunction "1_1") (pintype "passive"))
      (node (ref "COD_DROIT") (pin "2") (pinfunction "2_2") (pintype "passive"))
      (node (ref "COD_GAUCHE") (pin "2") (pinfunction "2_2") (pintype "passive"))
      (node (ref "COURSE_D_FER") (pin "1") (pinfunction "1_1") (pintype "passive"))
      (node (ref "COURSE_D_OUV") (pin "1") (pinfunction "1_1") (pintype "passive"))
      (node (ref "COURSE_G_FER") (pin "1") (pinfunction "1_1") (pintype "passive"))
      (node (ref "COURSE_G_OUV") (pin "1") (pinfunction "1_1") (pintype "passive"))
      (node (ref "D2") (pin "A") (pinfunction "A_A") (pintype "passive"))
      (node (ref "DC1") (pin "2") (pinfunction "GND_2") (pintype "passive"))
      (node (ref "DC2") (pin "2") (pinfunction "GND_2") (pintype "passive"))
      (node (ref "DC3") (pin "2") (pinfunction "GND_2") (pintype "passive"))
      (node (ref "DC4") (pin "2") (pinfunction "GND_2") (pintype "passive"))
      (node (ref "DEL_RASP") (pin "2") (pinfunction "KL_2") (pintype "passive"))
      (node (ref "IC1") (pin "1") (pinfunction "SEN_A_1") (pintype "input"))
      (node (ref "IC1") (pin "15") (pinfunction "SEN_B_15") (pintype "input"))
      (node (ref "IC1") (pin "8") (pinfunction "GND_8") (pintype "power_in"))
      (node (ref "IR_AR_D") (pin "1") (pinfunction "1_1") (pintype "passive"))
      (node (ref "IR_AR_G") (pin "1") (pinfunction "1_1") (pintype "passive"))
      (node (ref "IR_AV_D") (pin "1") (pinfunction "1_1") (pintype "passive"))
      (node (ref "IR_AV_G") (pin "1") (pinfunction "1_1") (pintype "passive"))
      (node (ref "JP1") (pin "1") (pinfunction "1_1") (pintype "passive"))
      (node (ref "JP2") (pin "1") (pinfunction "1_1") (pintype "passive"))
      (node (ref "JUMPER") (pin "1") (pinfunction "1_1") (pintype "passive"))
      (node (ref "LED1") (pin "K") (pinfunction "C_K") (pintype "passive"))
      (node (ref "MOTEUR_DROIT") (pin "4") (pinfunction "BREAK_4") (pintype "input"))
      (node (ref "MOTEUR_DROIT") (pin "7") (pinfunction "GND_7") (pintype "power_in"))
      (node (ref "MOTEUR_GAUCHE") (pin "4") (pinfunction "BREAK_4") (pintype "input"))
      (node (ref "MOTEUR_GAUCHE") (pin "7") (pinfunction "GND_7") (pintype "power_in"))
      (node (ref "R1") (pin "1") (pinfunction "1_1") (pintype "passive"))
      (node (ref "R10") (pin "E") (pinfunction "E_E") (pintype "passive"))
      (node (ref "R3") (pin "1") (pinfunction "1_1") (pintype "passive"))
      (node (ref "R4") (pin "2") (pinfunction "2_2") (pintype "passive"))
      (node (ref "R5") (pin "1") (pinfunction "1_1") (pintype "passive"))
      (node (ref "R6") (pin "1") (pinfunction "1_1") (pintype "passive"))
      (node (ref "R7") (pin "2") (pinfunction "2_2") (pintype "passive"))
      (node (ref "R8") (pin "2") (pinfunction "2_2") (pintype "passive"))
      (node (ref "R9") (pin "E") (pinfunction "E_E") (pintype "passive"))
      (node (ref "RASPBERRY") (pin "4") (pinfunction "4_4") (pintype "passive"))
      (node (ref "T1") (pin "E") (pinfunction "E_E") (pintype "passive"))
      (node (ref "T2") (pin "E") (pinfunction "E_E") (pintype "passive"))
      (node (ref "U$1") (pin "GND") (pinfunction "GND_GND") (pintype "bidirectional"))
      (node (ref "U$1") (pin "GND1") (pinfunction "GND1_GND1") (pintype "bidirectional"))
      (node (ref "U$1") (pin "GND2") (pinfunction "GND2_GND2") (pintype "bidirectional"))
      (node (ref "U$1") (pin "GND3") (pinfunction "GND3_GND3") (pintype "bidirectional"))
      (node (ref "U$1") (pin "GND4") (pinfunction "GND4_GND4") (pintype "bidirectional"))
      (node (ref "U$1") (pin "GND5") (pinfunction "GND5_GND5") (pintype "bidirectional"))
      (node (ref "U$1") (pin "GND6") (pinfunction "GND6_GND6") (pintype "bidirectional"))
      (node (ref "U$1") (pin "GND7") (pinfunction "GND7_GND7") (pintype "bidirectional"))
      (node (ref "U$1") (pin "GND8") (pinfunction "GND8_GND8") (pintype "bidirectional"))
      (node (ref "U$1") (pin "GND9") (pinfunction "GND9_GND9") (pintype "bidirectional"))
      (node (ref "U$2") (pin "11") (pinfunction "11_11") (pintype "bidirectional"))
      (node (ref "U$2") (pin "12") (pinfunction "12_12") (pintype "bidirectional"))
      (node (ref "U$2") (pin "13") (pinfunction "13_13") (pintype "bidirectional"))
      (node (ref "U$2") (pin "14") (pinfunction "14_14") (pintype "bidirectional"))
      (node (ref "U$2") (pin "15") (pinfunction "15_15") (pintype "bidirectional"))
      (node (ref "U$2") (pin "16") (pinfunction "16_16") (pintype "bidirectional"))
      (node (ref "U$2") (pin "17") (pinfunction "17_17") (pintype "bidirectional"))
      (node (ref "U$2") (pin "18") (pinfunction "18_18") (pintype "bidirectional"))
      (node (ref "U$2") (pin "19") (pinfunction "19_19") (pintype "bidirectional"))
      (node (ref "U$2") (pin "20") (pinfunction "20_20") (pintype "bidirectional"))
      (node (ref "UART_RASP") (pin "1") (pinfunction "1_1") (pintype "passive"))
    )
    (net (code "56") (name "Net-(ARRET_URGENCEA-KL)") (class "Default")
      (node (ref "ARRET_URGENCE") (pin "1") (pinfunction "KL_1") (pintype "passive"))
      (node (ref "ARRET_URGENCE_RASP") (pin "1") (pinfunction "KL_1") (pintype "passive"))
      (node (ref "BORNIER-LIPO") (pin "2") (pinfunction "KL_2") (pintype "passive"))
    )
    (net (code "57") (name "Net-(BORNIER-LIPOA-KL)") (class "Default")
      (node (ref "BORNIER-LIPO") (pin "1") (pinfunction "KL_1") (pintype "passive"))
      (node (ref "D2") (pin "C") (pinfunction "C_C") (pintype "passive"))
    )
    (net (code "58") (name "Net-(BORNIER_AXE_DA-KL)") (class "Default")
      (node (ref "BORNIER_AXE_D") (pin "1") (pinfunction "KL_1") (pintype "passive"))
      (node (ref "T2") (pin "C") (pinfunction "C_C") (pintype "passive"))
    )
    (net (code "59") (name "Net-(BORNIER_AXE_GA-KL)") (class "Default")
      (node (ref "BORNIER_AXE_G") (pin "1") (pinfunction "KL_1") (pintype "passive"))
      (node (ref "T1") (pin "C") (pinfunction "C_C") (pintype "passive"))
    )
    (net (code "60") (name "Net-(BORNIER_MOTEUR_DROITA-KL)") (class "Default")
      (node (ref "BORNIER_MOTEUR_DROIT") (pin "1") (pinfunction "KL_1") (pintype "passive"))
      (node (ref "C14") (pin "2") (pinfunction "2_2") (pintype "passive"))
      (node (ref "MOTEUR_DROIT") (pin "10") (pinfunction "OUTPUT2_10") (pintype "output"))
    )
    (net (code "61") (name "Net-(BORNIER_MOTEUR_DROITB-KL)") (class "Default")
      (node (ref "BORNIER_MOTEUR_DROIT") (pin "2") (pinfunction "KL_2") (pintype "passive"))
      (node (ref "C13") (pin "2") (pinfunction "2_2") (pintype "passive"))
      (node (ref "MOTEUR_DROIT") (pin "2") (pinfunction "OUTPUT1_2") (pintype "output"))
    )
    (net (code "62") (name "Net-(BORNIER_MOTEUR_GAUCHEA-KL)") (class "Default")
      (node (ref "BORNIER_MOTEUR_GAUCHE") (pin "1") (pinfunction "KL_1") (pintype "passive"))
      (node (ref "C12") (pin "2") (pinfunction "2_2") (pintype "passive"))
      (node (ref "MOTEUR_GAUCHE") (pin "10") (pinfunction "OUTPUT2_10") (pintype "output"))
    )
    (net (code "63") (name "Net-(BORNIER_MOTEUR_GAUCHEB-KL)") (class "Default")
      (node (ref "BORNIER_MOTEUR_GAUCHE") (pin "2") (pinfunction "KL_2") (pintype "passive"))
      (node (ref "C11") (pin "2") (pinfunction "2_2") (pintype "passive"))
      (node (ref "MOTEUR_GAUCHE") (pin "2") (pinfunction "OUTPUT1_2") (pintype "output"))
    )
    (net (code "64") (name "Net-(BORNIER_PORTE_DA-KL)") (class "Default")
      (node (ref "BORNIER_PORTE_D") (pin "1") (pinfunction "KL_1") (pintype "passive"))
      (node (ref "IC1") (pin "14") (pinfunction "OUT4_14") (pintype "output"))
    )
    (net (code "65") (name "Net-(BORNIER_PORTE_DB-KL)") (class "Default")
      (node (ref "BORNIER_PORTE_D") (pin "2") (pinfunction "KL_2") (pintype "passive"))
      (node (ref "IC1") (pin "13") (pinfunction "OUT3_13") (pintype "output"))
    )
    (net (code "66") (name "Net-(BORNIER_PORTE_GA-KL)") (class "Default")
      (node (ref "BORNIER_PORTE_G") (pin "1") (pinfunction "KL_1") (pintype "passive"))
      (node (ref "IC1") (pin "2") (pinfunction "OUT1_2") (pintype "output"))
    )
    (net (code "67") (name "Net-(BORNIER_PORTE_GB-KL)") (class "Default")
      (node (ref "BORNIER_PORTE_G") (pin "2") (pinfunction "KL_2") (pintype "passive"))
      (node (ref "IC1") (pin "3") (pinfunction "OUT2_3") (pintype "output"))
    )
    (net (code "68") (name "Net-(DC1-VIN)") (class "Default")
      (node (ref "C5") (pin "+") (pinfunction "+_+") (pintype "passive"))
      (node (ref "DC1") (pin "1") (pinfunction "VIN_1") (pintype "passive"))
      (node (ref "L1") (pin "2") (pinfunction "2_2") (pintype "passive"))
    )
    (net (code "69") (name "Net-(DC2-VIN)") (class "Default")
      (node (ref "C16") (pin "+") (pinfunction "+_+") (pintype "passive"))
      (node (ref "DC2") (pin "1") (pinfunction "VIN_1") (pintype "passive"))
      (node (ref "L2") (pin "2") (pinfunction "2_2") (pintype "passive"))
    )
    (net (code "70") (name "Net-(DC3-VIN)") (class "Default")
      (node (ref "C18") (pin "+") (pinfunction "+_+") (pintype "passive"))
      (node (ref "DC3") (pin "1") (pinfunction "VIN_1") (pintype "passive"))
      (node (ref "L3") (pin "2") (pinfunction "2_2") (pintype "passive"))
    )
    (net (code "71") (name "Net-(DC4-VIN)") (class "Default")
      (node (ref "C20") (pin "+") (pinfunction "+_+") (pintype "passive"))
      (node (ref "DC4") (pin "1") (pinfunction "VIN_1") (pintype "passive"))
      (node (ref "L4") (pin "2") (pinfunction "2_2") (pintype "passive"))
    )
    (net (code "72") (name "Net-(DEL_RASPA-KL)") (class "Default")
      (node (ref "DEL_RASP") (pin "1") (pinfunction "KL_1") (pintype "passive"))
      (node (ref "R22") (pin "2") (pinfunction "2_2") (pintype "passive"))
    )
    (net (code "73") (name "Net-(LED1-PadA)") (class "Default")
      (node (ref "LED1") (pin "A") (pinfunction "A_A") (pintype "passive"))
      (node (ref "R11") (pin "2") (pinfunction "2_2") (pintype "passive"))
    )
    (net (code "74") (name "Net-(MOTEUR_DROIT-BOOTSTRAP1)") (class "Default")
      (node (ref "C13") (pin "1") (pinfunction "1_1") (pintype "passive"))
      (node (ref "MOTEUR_DROIT") (pin "1") (pinfunction "BOOTSTRAP1_1") (pintype "input"))
    )
    (net (code "75") (name "Net-(MOTEUR_DROIT-BOOTSTRAP2)") (class "Default")
      (node (ref "C14") (pin "1") (pinfunction "1_1") (pintype "passive"))
      (node (ref "MOTEUR_DROIT") (pin "11") (pinfunction "BOOTSTRAP2_11") (pintype "input"))
    )
    (net (code "76") (name "Net-(MOTEUR_GAUCHE-BOOTSTRAP1)") (class "Default")
      (node (ref "C11") (pin "1") (pinfunction "1_1") (pintype "passive"))
      (node (ref "MOTEUR_GAUCHE") (pin "1") (pinfunction "BOOTSTRAP1_1") (pintype "input"))
    )
    (net (code "77") (name "Net-(MOTEUR_GAUCHE-BOOTSTRAP2)") (class "Default")
      (node (ref "C12") (pin "1") (pinfunction "1_1") (pintype "passive"))
      (node (ref "MOTEUR_GAUCHE") (pin "11") (pinfunction "BOOTSTRAP2_11") (pintype "input"))
    )
    (net (code "78") (name "Net-(R9-PadS)") (class "Default")
      (node (ref "R9") (pin "S") (pinfunction "S_S") (pintype "passive"))
      (node (ref "T1") (pin "B") (pinfunction "B_B") (pintype "passive"))
    )
    (net (code "79") (name "Net-(R10-PadS)") (class "Default")
      (node (ref "R10") (pin "S") (pinfunction "S_S") (pintype "passive"))
      (node (ref "T2") (pin "B") (pinfunction "B_B") (pintype "passive"))
    )
    (net (code "80") (name "Net-(R12-Pad1)") (class "Default")
      (node (ref "R12") (pin "1") (pinfunction "1_1") (pintype "passive"))
      (node (ref "U$2") (pin "10") (pinfunction "10_10") (pintype "bidirectional"))
    )
    (net (code "81") (name "Net-(R13-Pad1)") (class "Default")
      (node (ref "R13") (pin "1") (pinfunction "1_1") (pintype "passive"))
      (node (ref "U$2") (pin "9") (pinfunction "9_9") (pintype "bidirectional"))
    )
    (net (code "82") (name "Net-(R14-Pad1)") (class "Default")
      (node (ref "R14") (pin "1") (pinfunction "1_1") (pintype "passive"))
      (node (ref "U$2") (pin "8") (pinfunction "8_8") (pintype "bidirectional"))
    )
    (net (code "83") (name "Net-(R15-Pad1)") (class "Default")
      (node (ref "R15") (pin "1") (pinfunction "1_1") (pintype "passive"))
      (node (ref "U$2") (pin "7") (pinfunction "7_7") (pintype "bidirectional"))
    )
    (net (code "84") (name "Net-(R16-Pad1)") (class "Default")
      (node (ref "R16") (pin "1") (pinfunction "1_1") (pintype "passive"))
      (node (ref "U$2") (pin "6") (pinfunction "6_6") (pintype "bidirectional"))
    )
    (net (code "85") (name "Net-(R17-Pad1)") (class "Default")
      (node (ref "R17") (pin "1") (pinfunction "1_1") (pintype "passive"))
      (node (ref "U$2") (pin "5") (pinfunction "5_5") (pintype "bidirectional"))
    )
    (net (code "86") (name "Net-(R18-Pad1)") (class "Default")
      (node (ref "R18") (pin "1") (pinfunction "1_1") (pintype "passive"))
      (node (ref "U$2") (pin "4") (pinfunction "4_4") (pintype "bidirectional"))
    )
    (net (code "87") (name "Net-(R19-Pad1)") (class "Default")
      (node (ref "R19") (pin "1") (pinfunction "1_1") (pintype "passive"))
      (node (ref "U$2") (pin "3") (pinfunction "3_3") (pintype "bidirectional"))
    )
    (net (code "88") (name "Net-(R20-Pad1)") (class "Default")
      (node (ref "R20") (pin "1") (pinfunction "1_1") (pintype "passive"))
      (node (ref "U$2") (pin "2") (pinfunction "2_2") (pintype "bidirectional"))
    )
    (net (code "89") (name "Net-(R21-Pad1)") (class "Default")
      (node (ref "R21") (pin "1") (pinfunction "1_1") (pintype "passive"))
      (node (ref "U$2") (pin "1") (pinfunction "1_1") (pintype "bidirectional"))
    )
    (net (code "90") (name "unconnected-(BOB-08745-PadRXI-1)") (class "Default")
      (node (ref "BOB-08745") (pin "RXI-1") (pinfunction "RXI-1_RXI-1") (pintype "bidirectional"))
    )
    (net (code "91") (name "unconnected-(BOB-08745-PadRXI-2)") (class "Default")
      (node (ref "BOB-08745") (pin "RXI-2") (pinfunction "RXI-2_RXI-2") (pintype "bidirectional"))
    )
    (net (code "92") (name "unconnected-(BOB-08745-PadRXO-1)") (class "Default")
      (node (ref "BOB-08745") (pin "RXO-1") (pinfunction "RXO-1_RXO-1") (pintype "bidirectional"))
    )
    (net (code "93") (name "unconnected-(BOB-08745-PadRXO-2)") (class "Default")
      (node (ref "BOB-08745") (pin "RXO-2") (pinfunction "RXO-2_RXO-2") (pintype "bidirectional"))
    )
    (net (code "94") (name "unconnected-(BOB-08745-PadTXI-2)") (class "Default")
      (node (ref "BOB-08745") (pin "TXI-2") (pinfunction "TXI-2_TXI-2") (pintype "bidirectional"))
    )
    (net (code "95") (name "unconnected-(BOB-08745-PadTXO-2)") (class "Default")
      (node (ref "BOB-08745") (pin "TXO-2") (pinfunction "TXO-2_TXO-2") (pintype "bidirectional"))
    )
    (net (code "96") (name "unconnected-(MOTEUR_DROIT-SENSE-Pad8)") (class "Default")
      (node (ref "MOTEUR_DROIT") (pin "8") (pinfunction "SENSE_8") (pintype "output"))
    )
    (net (code "97") (name "unconnected-(MOTEUR_DROIT-THERMAL-Pad9)") (class "Default")
      (node (ref "MOTEUR_DROIT") (pin "9") (pinfunction "THERMAL_9") (pintype "output"))
    )
    (net (code "98") (name "unconnected-(MOTEUR_GAUCHE-SENSE-Pad8)") (class "Default")
      (node (ref "MOTEUR_GAUCHE") (pin "8") (pinfunction "SENSE_8") (pintype "output"))
    )
    (net (code "99") (name "unconnected-(MOTEUR_GAUCHE-THERMAL-Pad9)") (class "Default")
      (node (ref "MOTEUR_GAUCHE") (pin "9") (pinfunction "THERMAL_9") (pintype "output"))
    )
    (net (code "100") (name "unconnected-(RASPBERRY-Pad2)") (class "Default")
      (node (ref "RASPBERRY") (pin "2") (pinfunction "2_2") (pintype "passive"))
    )
    (net (code "101") (name "unconnected-(RASPBERRY-Pad3)") (class "Default")
      (node (ref "RASPBERRY") (pin "3") (pinfunction "3_3") (pintype "passive"))
    )
    (net (code "102") (name "unconnected-(U$1-PadBOOT0)") (class "Default")
      (node (ref "U$1") (pin "BOOT0") (pinfunction "BOOT0_BOOT0") (pintype "bidirectional"))
    )
    (net (code "103") (name "unconnected-(U$1-PadNC)") (class "Default")
      (node (ref "U$1") (pin "NC") (pinfunction "NC_NC") (pintype "bidirectional"))
    )
    (net (code "104") (name "unconnected-(U$1-PadNRST)") (class "Default")
      (node (ref "U$1") (pin "NRST") (pinfunction "NRST_NRST") (pintype "bidirectional"))
    )
    (net (code "105") (name "unconnected-(U$1-PadPA8)") (class "Default")
      (node (ref "U$1") (pin "PA8") (pinfunction "PA8_PA8") (pintype "bidirectional"))
    )
    (net (code "106") (name "unconnected-(U$1-PadPA9)") (class "Default")
      (node (ref "U$1") (pin "PA9") (pinfunction "PA9_PA9") (pintype "bidirectional"))
    )
    (net (code "107") (name "unconnected-(U$1-PadPA13)") (class "Default")
      (node (ref "U$1") (pin "PA13") (pinfunction "PA13_PA13") (pintype "bidirectional"))
    )
    (net (code "108") (name "unconnected-(U$1-PadPA14)") (class "Default")
      (node (ref "U$1") (pin "PA14") (pinfunction "PA14_PA14") (pintype "bidirectional"))
    )
    (net (code "109") (name "unconnected-(U$1-PadPB1)") (class "Default")
      (node (ref "U$1") (pin "PB1") (pinfunction "PB1_PB1") (pintype "bidirectional"))
    )
    (net (code "110") (name "unconnected-(U$1-PadPB3)") (class "Default")
      (node (ref "U$1") (pin "PB3") (pinfunction "PB3_PB3") (pintype "bidirectional"))
    )
    (net (code "111") (name "unconnected-(U$1-PadPB8)") (class "Default")
      (node (ref "U$1") (pin "PB8") (pinfunction "PB8_PB8") (pintype "bidirectional"))
    )
    (net (code "112") (name "unconnected-(U$1-PadPB9)") (class "Default")
      (node (ref "U$1") (pin "PB9") (pinfunction "PB9_PB9") (pintype "bidirectional"))
    )
    (net (code "113") (name "unconnected-(U$1-PadPB10)") (class "Default")
      (node (ref "U$1") (pin "PB10") (pinfunction "PB10_PB10") (pintype "bidirectional"))
    )
    (net (code "114") (name "unconnected-(U$1-PadPB11)") (class "Default")
      (node (ref "U$1") (pin "PB11") (pinfunction "PB11_PB11") (pintype "bidirectional"))
    )
    (net (code "115") (name "unconnected-(U$1-PadPB12)") (class "Default")
      (node (ref "U$1") (pin "PB12") (pinfunction "PB12_PB12") (pintype "bidirectional"))
    )
    (net (code "116") (name "unconnected-(U$1-PadPB13)") (class "Default")
      (node (ref "U$1") (pin "PB13") (pinfunction "PB13_PB13") (pintype "bidirectional"))
    )
    (net (code "117") (name "unconnected-(U$1-PadPB14)") (class "Default")
      (node (ref "U$1") (pin "PB14") (pinfunction "PB14_PB14") (pintype "bidirectional"))
    )
    (net (code "118") (name "unconnected-(U$1-PadPB15)") (class "Default")
      (node (ref "U$1") (pin "PB15") (pinfunction "PB15_PB15") (pintype "bidirectional"))
    )
    (net (code "119") (name "unconnected-(U$1-PadPC6)") (class "Default")
      (node (ref "U$1") (pin "PC6") (pinfunction "PC6_PC6") (pintype "bidirectional"))
    )
    (net (code "120") (name "unconnected-(U$1-PadPC10)") (class "Default")
      (node (ref "U$1") (pin "PC10") (pinfunction "PC10_PC10") (pintype "bidirectional"))
    )
    (net (code "121") (name "unconnected-(U$1-PadPC12)") (class "Default")
      (node (ref "U$1") (pin "PC12") (pinfunction "PC12_PC12") (pintype "bidirectional"))
    )
    (net (code "122") (name "unconnected-(U$1-PadPD1)") (class "Default")
      (node (ref "U$1") (pin "PD1") (pinfunction "PD1_PD1") (pintype "bidirectional"))
    )
    (net (code "123") (name "unconnected-(U$1-PadPD3)") (class "Default")
      (node (ref "U$1") (pin "PD3") (pinfunction "PD3_PD3") (pintype "bidirectional"))
    )
    (net (code "124") (name "unconnected-(U$1-PadPD5)") (class "Default")
      (node (ref "U$1") (pin "PD5") (pinfunction "PD5_PD5") (pintype "bidirectional"))
    )
    (net (code "125") (name "unconnected-(U$1-PadPD7)") (class "Default")
      (node (ref "U$1") (pin "PD7") (pinfunction "PD7_PD7") (pintype "bidirectional"))
    )
    (net (code "126") (name "unconnected-(U$1-PadPD8)") (class "Default")
      (node (ref "U$1") (pin "PD8") (pinfunction "PD8_PD8") (pintype "bidirectional"))
    )
    (net (code "127") (name "unconnected-(U$1-PadPD9)") (class "Default")
      (node (ref "U$1") (pin "PD9") (pinfunction "PD9_PD9") (pintype "bidirectional"))
    )
    (net (code "128") (name "unconnected-(U$1-PadPD10)") (class "Default")
      (node (ref "U$1") (pin "PD10") (pinfunction "PD10_PD10") (pintype "bidirectional"))
    )
    (net (code "129") (name "unconnected-(U$1-PadPD11)") (class "Default")
      (node (ref "U$1") (pin "PD11") (pinfunction "PD11_PD11") (pintype "bidirectional"))
    )
    (net (code "130") (name "unconnected-(U$1-PadPD13)") (class "Default")
      (node (ref "U$1") (pin "PD13") (pinfunction "PD13_PD13") (pintype "bidirectional"))
    )
    (net (code "131") (name "unconnected-(U$1-PadPD15)") (class "Default")
      (node (ref "U$1") (pin "PD15") (pinfunction "PD15_PD15") (pintype "bidirectional"))
    )
    (net (code "132") (name "unconnected-(U$1-PadPE0)") (class "Default")
      (node (ref "U$1") (pin "PE0") (pinfunction "PE0_PE0") (pintype "bidirectional"))
    )
    (net (code "133") (name "unconnected-(U$1-PadPE2)") (class "Default")
      (node (ref "U$1") (pin "PE2") (pinfunction "PE2_PE2") (pintype "bidirectional"))
    )
    (net (code "134") (name "unconnected-(U$1-PadPE7)") (class "Default")
      (node (ref "U$1") (pin "PE7") (pinfunction "PE7_PE7") (pintype "bidirectional"))
    )
    (net (code "135") (name "unconnected-(U$1-PadPE8)") (class "Default")
      (node (ref "U$1") (pin "PE8") (pinfunction "PE8_PE8") (pintype "bidirectional"))
    )
    (net (code "136") (name "unconnected-(U$1-PadPE10)") (class "Default")
      (node (ref "U$1") (pin "PE10") (pinfunction "PE10_PE10") (pintype "bidirectional"))
    )
    (net (code "137") (name "unconnected-(U$1-PadPE12)") (class "Default")
      (node (ref "U$1") (pin "PE12") (pinfunction "PE12_PE12") (pintype "bidirectional"))
    )
    (net (code "138") (name "unconnected-(U$1-PadPE14)") (class "Default")
      (node (ref "U$1") (pin "PE14") (pinfunction "PE14_PE14") (pintype "bidirectional"))
    )
    (net (code "139") (name "unconnected-(U$1-PadVDD1)") (class "Default")
      (node (ref "U$1") (pin "VDD1") (pinfunction "VDD1_VDD1") (pintype "bidirectional"))
    )
    (net (code "140") (name "unconnected-(U$1-PadVDD2)") (class "Default")
      (node (ref "U$1") (pin "VDD2") (pinfunction "VDD2_VDD2") (pintype "bidirectional"))
    )
    (net (code "141") (name "unconnected-(U$1-PadVDD3)") (class "Default")
      (node (ref "U$1") (pin "VDD3") (pinfunction "VDD3_VDD3") (pintype "bidirectional"))
    )
    (net (code "142") (name "unconnected-(U$1-PadVDD4)") (class "Default")
      (node (ref "U$1") (pin "VDD4") (pinfunction "VDD4_VDD4") (pintype "bidirectional"))
    )
  )
)
